# RFTP0603.net
KiCad netlist of a schematic drawn in Altium Designer
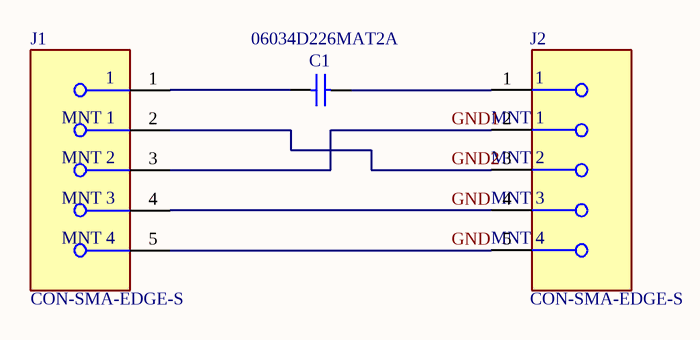
[diagram p0: RFTP0603.SchDoc]

(export (version "E")
  (design (tool "Eeschema 10.0.6"))
  (components
    (comp (ref "C1")
      (value "06034D226MAT2A")
      (footprint "CAPC1608X90X35ML15T15")
      (fields (field (name "MANUFACTURER") "AVX Interconnect / Elco"))
      (libsource (lib "Altium Content Vault") (part "CAP"))
    )
    (comp (ref "J1")
      (value "CON-SMA-EDGE-S")
      (footprint "FP-CON-SMA-EDGE-S-MFG")
      (description "CONN SMA JACK STR EDGE MNT")
      (fields
        (field (name "OCTOPART") "https://octopart.com/con-sma-edge-s-rf+solutions-70967450")
        (field (name "MANUFACTURER") "RF Solutions Ltd.")
      )
      (libsource (lib "") (part "a163d97a771fcdd2fd1f1a9264c171f_1"))
    )
    (comp (ref "J2")
      (value "CON-SMA-EDGE-S")
      (footprint "FP-CON-SMA-EDGE-S-MFG")
      (description "CONN SMA JACK STR EDGE MNT")
      (fields
        (field (name "OCTOPART") "https://octopart.com/con-sma-edge-s-rf+solutions-70967450")
        (field (name "MANUFACTURER") "RF Solutions Ltd.")
      )
      (libsource (lib "Altium Content Vault") (part "a163d97a771fcdd2fd1f1a9264c171f"))
    )
  )
  (nets
    (net (code "1") (name "/GND") (class "Default")
      (node (ref "J1") (pin "4") (pinfunction "MNT_3_4") (pintype "passive"))
      (node (ref "J1") (pin "5") (pinfunction "MNT_4_5") (pintype "passive"))
      (node (ref "J2") (pin "4") (pinfunction "MNT_3_4") (pintype "passive"))
      (node (ref "J2") (pin "5") (pinfunction "MNT_4_5") (pintype "passive"))
    )
    (net (code "2") (name "/GND1") (class "Default")
      (node (ref "J1") (pin "3") (pinfunction "MNT_2_3") (pintype "passive"))
      (node (ref "J2") (pin "2") (pinfunction "MNT_1_2") (pintype "passive"))
    )
    (net (code "3") (name "/GND2") (class "Default")
      (node (ref "J1") (pin "2") (pinfunction "MNT_1_2") (pintype "passive"))
      (node (ref "J2") (pin "3") (pinfunction "MNT_2_3") (pintype "passive"))
    )
    (net (code "4") (name "Net-(C1-Pad1)") (class "Default")
      (node (ref "C1") (pin "1") (pinfunction "1_1") (pintype "passive"))
      (node (ref "J1") (pin "1") (pinfunction "1_1") (pintype "passive"))
    )
    (net (code "5") (name "Net-(C1-Pad2)") (class "Default")
      (node (ref "C1") (pin "2") (pinfunction "2_2") (pintype "passive"))
      (node (ref "J2") (pin "1") (pinfunction "1_1") (pintype "passive"))
    )
  )
)
